# condemore.net
KiCad netlist of a schematic drawn in EAGLE
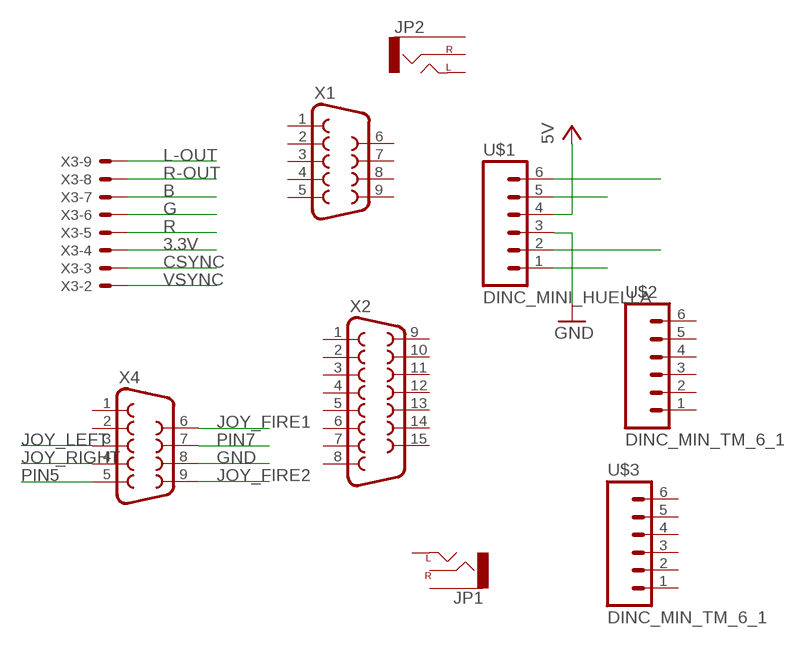
[diagram p0: schematic, sheet 1]

(export (version "E")
  (design (tool "Eeschema 10.0.6"))
  (components
    (comp (ref "JP1")
      (value "AUDIO-JACK_HUELLAPTH")
      (footprint "eagle-import:AUDIO-JACK_HUELLA")
      (libsource (lib "eagle-import") (part "AUDIO-JACK_HUELLAPTH"))
    )
    (comp (ref "JP2")
      (value "AUDIO-JACKPTH")
      (footprint "eagle-import:AUDIO-JACK")
      (libsource (lib "eagle-import") (part "AUDIO-JACKPTH"))
    )
    (comp (ref "U$1")
      (value "DINC_MINI_HUELLA")
      (footprint "eagle-import:DINC_MIN_TM_6_1PRIMARY_HUELLA")
      (libsource (lib "eagle-import") (part "DINC_MINI_HUELLA"))
    )
    (comp (ref "U$2")
      (value "DINC_MIN_TM_6_1")
      (footprint "eagle-import:DINC_MIN_TM_6_1PRIMARY")
      (libsource (lib "eagle-import") (part "DINC_MIN_TM_6_1"))
    )
    (comp (ref "U$3")
      (value "DINC_MIN_TM_6_1")
      (footprint "eagle-import:DINC_MIN_TM_6_1PRIMARY")
      (libsource (lib "eagle-import") (part "DINC_MIN_TM_6_1"))
    )
    (comp (ref "X1")
      (value "DB9MALE")
      (footprint "eagle-import:DB9_MALE")
      (libsource (lib "eagle-import") (part "DB9MALE"))
    )
    (comp (ref "X2")
      (value "F15HDH")
      (footprint "eagle-import:HDF15H")
      (libsource (lib "eagle-import") (part "F15HDH"))
    )
    (comp (ref "X3")
      (value "53048-09_HUELLA")
      (footprint "eagle-import:53048-09_HUELLA")
      (fields (field (name "MPN") "53048-0910"))
      (libsource (lib "eagle-import") (part "53?-09_HUELLA048"))
    )
    (comp (ref "X4")
      (value "DB9MALE")
      (footprint "eagle-import:DB9_MALE")
      (libsource (lib "eagle-import") (part "SparkFun-Connectors_huella_DB9MALE"))
    )
  )
  (nets
    (net (code "1") (name "/3.3V") (class "Default")
      (node (ref "X3") (pin "4") (pinfunction "S_4") (pintype "passive"))
    )
    (net (code "2") (name "/B") (class "Default")
      (node (ref "X3") (pin "7") (pinfunction "S_7") (pintype "passive"))
    )
    (net (code "3") (name "/CSYNC") (class "Default")
      (node (ref "X3") (pin "3") (pinfunction "S_3") (pintype "passive"))
    )
    (net (code "4") (name "/G") (class "Default")
      (node (ref "X3") (pin "6") (pinfunction "S_6") (pintype "passive"))
    )
    (net (code "5") (name "/JOY_FIRE1") (class "Default")
      (node (ref "X4") (pin "6") (pinfunction "6_6") (pintype "passive"))
    )
    (net (code "6") (name "/JOY_FIRE2") (class "Default")
      (node (ref "X4") (pin "9") (pinfunction "9_9") (pintype "passive"))
    )
    (net (code "7") (name "/JOY_LEFT") (class "Default")
      (node (ref "X4") (pin "3") (pinfunction "3_3") (pintype "passive"))
    )
    (net (code "8") (name "/JOY_RIGHT") (class "Default")
      (node (ref "X4") (pin "4") (pinfunction "4_4") (pintype "passive"))
    )
    (net (code "9") (name "/L-OUT") (class "Default")
      (node (ref "X3") (pin "9") (pinfunction "S_9") (pintype "passive"))
    )
    (net (code "10") (name "/PIN5") (class "Default")
      (node (ref "X4") (pin "5") (pinfunction "5_5") (pintype "passive"))
    )
    (net (code "11") (name "/PIN7") (class "Default")
      (node (ref "X4") (pin "7") (pinfunction "7_7") (pintype "passive"))
    )
    (net (code "12") (name "/R") (class "Default")
      (node (ref "X3") (pin "5") (pinfunction "S_5") (pintype "passive"))
    )
    (net (code "13") (name "/R-OUT") (class "Default")
      (node (ref "X3") (pin "8") (pinfunction "S_8") (pintype "passive"))
    )
    (net (code "14") (name "/VSYNC") (class "Default")
      (node (ref "X3") (pin "2") (pinfunction "S_2") (pintype "passive"))
    )
    (net (code "15") (name "5V") (class "Default")
      (node (ref "U$1") (pin "4") (pinfunction "4_4") (pintype "passive"))
    )
    (net (code "16") (name "GND") (class "Default")
      (node (ref "U$1") (pin "3") (pinfunction "3_3") (pintype "passive"))
      (node (ref "X4") (pin "8") (pinfunction "8_8") (pintype "passive"))
    )
    (net (code "17") (name "unconnected-(JP1-LEFT-PadTIP)") (class "Default")
      (node (ref "JP1") (pin "TIP") (pinfunction "LEFT_TIP") (pintype "bidirectional"))
    )
    (net (code "18") (name "unconnected-(JP2-LEFT-PadTIP)") (class "Default")
      (node (ref "JP2") (pin "TIP") (pinfunction "LEFT_TIP") (pintype "bidirectional"))
    )
    (net (code "19") (name "unconnected-(JP2-PadSLEEVE)") (class "Default")
      (node (ref "JP2") (pin "SLEEVE") (pinfunction "SLEEVE_SLEEVE") (pintype "bidirectional"))
    )
    (net (code "20") (name "unconnected-(JP2-RIGHT-PadRING)") (class "Default")
      (node (ref "JP2") (pin "RING") (pinfunction "RIGHT_RING") (pintype "bidirectional"))
    )
    (net (code "21") (name "unconnected-(U$1-Pad1)") (class "Default")
      (node (ref "U$1") (pin "1") (pinfunction "1_1") (pintype "passive"))
    )
    (net (code "22") (name "unconnected-(U$1-Pad2)") (class "Default")
      (node (ref "U$1") (pin "2") (pinfunction "2_2") (pintype "passive"))
    )
    (net (code "23") (name "unconnected-(U$1-Pad5)") (class "Default")
      (node (ref "U$1") (pin "5") (pinfunction "5_5") (pintype "passive"))
    )
    (net (code "24") (name "unconnected-(U$1-Pad6)") (class "Default")
      (node (ref "U$1") (pin "6") (pinfunction "6_6") (pintype "passive"))
    )
    (net (code "25") (name "unconnected-(U$2-Pad1)") (class "Default")
      (node (ref "U$2") (pin "1") (pinfunction "1_1") (pintype "passive"))
    )
    (net (code "26") (name "unconnected-(U$2-Pad2)") (class "Default")
      (node (ref "U$2") (pin "2") (pinfunction "2_2") (pintype "passive"))
    )
    (net (code "27") (name "unconnected-(U$2-Pad3)") (class "Default")
      (node (ref "U$2") (pin "3") (pinfunction "3_3") (pintype "passive"))
    )
    (net (code "28") (name "unconnected-(U$2-Pad4)") (class "Default")
      (node (ref "U$2") (pin "4") (pinfunction "4_4") (pintype "passive"))
    )
    (net (code "29") (name "unconnected-(U$2-Pad5)") (class "Default")
      (node (ref "U$2") (pin "5") (pinfunction "5_5") (pintype "passive"))
    )
    (net (code "30") (name "unconnected-(U$2-Pad6)") (class "Default")
      (node (ref "U$2") (pin "6") (pinfunction "6_6") (pintype "passive"))
    )
    (net (code "31") (name "unconnected-(U$3-Pad1)") (class "Default")
      (node (ref "U$3") (pin "1") (pinfunction "1_1") (pintype "passive"))
    )
    (net (code "32") (name "unconnected-(U$3-Pad2)") (class "Default")
      (node (ref "U$3") (pin "2") (pinfunction "2_2") (pintype "passive"))
    )
    (net (code "33") (name "unconnected-(U$3-Pad3)") (class "Default")
      (node (ref "U$3") (pin "3") (pinfunction "3_3") (pintype "passive"))
    )
    (net (code "34") (name "unconnected-(U$3-Pad4)") (class "Default")
      (node (ref "U$3") (pin "4") (pinfunction "4_4") (pintype "passive"))
    )
    (net (code "35") (name "unconnected-(U$3-Pad5)") (class "Default")
      (node (ref "U$3") (pin "5") (pinfunction "5_5") (pintype "passive"))
    )
    (net (code "36") (name "unconnected-(U$3-Pad6)") (class "Default")
      (node (ref "U$3") (pin "6") (pinfunction "6_6") (pintype "passive"))
    )
    (net (code "37") (name "unconnected-(X1-Pad1)") (class "Default")
      (node (ref "X1") (pin "1") (pinfunction "1_1") (pintype "passive"))
    )
    (net (code "38") (name "unconnected-(X1-Pad2)") (class "Default")
      (node (ref "X1") (pin "2") (pinfunction "2_2") (pintype "passive"))
    )
    (net (code "39") (name "unconnected-(X1-Pad3)") (class "Default")
      (node (ref "X1") (pin "3") (pinfunction "3_3") (pintype "passive"))
    )
    (net (code "40") (name "unconnected-(X1-Pad4)") (class "Default")
      (node (ref "X1") (pin "4") (pinfunction "4_4") (pintype "passive"))
    )
    (net (code "41") (name "unconnected-(X1-Pad5)") (class "Default")
      (node (ref "X1") (pin "5") (pinfunction "5_5") (pintype "passive"))
    )
    (net (code "42") (name "unconnected-(X1-Pad6)") (class "Default")
      (node (ref "X1") (pin "6") (pinfunction "6_6") (pintype "passive"))
    )
    (net (code "43") (name "unconnected-(X1-Pad7)") (class "Default")
      (node (ref "X1") (pin "7") (pinfunction "7_7") (pintype "passive"))
    )
    (net (code "44") (name "unconnected-(X1-Pad8)") (class "Default")
      (node (ref "X1") (pin "8") (pinfunction "8_8") (pintype "passive"))
    )
    (net (code "45") (name "unconnected-(X1-Pad9)") (class "Default")
      (node (ref "X1") (pin "9") (pinfunction "9_9") (pintype "passive"))
    )
    (net (code "46") (name "unconnected-(X2-Pad1)") (class "Default")
      (node (ref "X2") (pin "1") (pinfunction "1_1") (pintype "passive"))
    )
    (net (code "47") (name "unconnected-(X2-Pad2)") (class "Default")
      (node (ref "X2") (pin "2") (pinfunction "2_2") (pintype "passive"))
    )
    (net (code "48") (name "unconnected-(X2-Pad3)") (class "Default")
      (node (ref "X2") (pin "3") (pinfunction "3_3") (pintype "passive"))
    )
    (net (code "49") (name "unconnected-(X2-Pad4)") (class "Default")
      (node (ref "X2") (pin "4") (pinfunction "4_4") (pintype "passive"))
    )
    (net (code "50") (name "unconnected-(X2-Pad5)") (class "Default")
      (node (ref "X2") (pin "5") (pinfunction "5_5") (pintype "passive"))
    )
    (net (code "51") (name "unconnected-(X2-Pad6)") (class "Default")
      (node (ref "X2") (pin "6") (pinfunction "6_6") (pintype "passive"))
    )
    (net (code "52") (name "unconnected-(X2-Pad7)") (class "Default")
      (node (ref "X2") (pin "7") (pinfunction "7_7") (pintype "passive"))
    )
    (net (code "53") (name "unconnected-(X2-Pad8)") (class "Default")
      (node (ref "X2") (pin "8") (pinfunction "8_8") (pintype "passive"))
    )
    (net (code "54") (name "unconnected-(X2-Pad9)") (class "Default")
      (node (ref "X2") (pin "9") (pinfunction "9_9") (pintype "passive"))
    )
    (net (code "55") (name "unconnected-(X2-Pad10)") (class "Default")
      (node (ref "X2") (pin "10") (pinfunction "10_10") (pintype "passive"))
    )
    (net (code "56") (name "unconnected-(X2-Pad11)") (class "Default")
      (node (ref "X2") (pin "11") (pinfunction "11_11") (pintype "passive"))
    )
    (net (code "57") (name "unconnected-(X2-Pad12)") (class "Default")
      (node (ref "X2") (pin "12") (pinfunction "12_12") (pintype "passive"))
    )
    (net (code "58") (name "unconnected-(X2-Pad13)") (class "Default")
      (node (ref "X2") (pin "13") (pinfunction "13_13") (pintype "passive"))
    )
    (net (code "59") (name "unconnected-(X2-Pad14)") (class "Default")
      (node (ref "X2") (pin "14") (pinfunction "14_14") (pintype "passive"))
    )
    (net (code "60") (name "unconnected-(X2-Pad15)") (class "Default")
      (node (ref "X2") (pin "15") (pinfunction "15_15") (pintype "passive"))
    )
    (net (code "61") (name "unconnected-(X4-Pad1)") (class "Default")
      (node (ref "X4") (pin "1") (pinfunction "1_1") (pintype "passive"))
    )
    (net (code "62") (name "unconnected-(X4-Pad2)") (class "Default")
      (node (ref "X4") (pin "2") (pinfunction "2_2") (pintype "passive"))
    )
  )
)
